# Glog_5G_LTE.net
KiCad netlist of a schematic drawn in Altium Designer
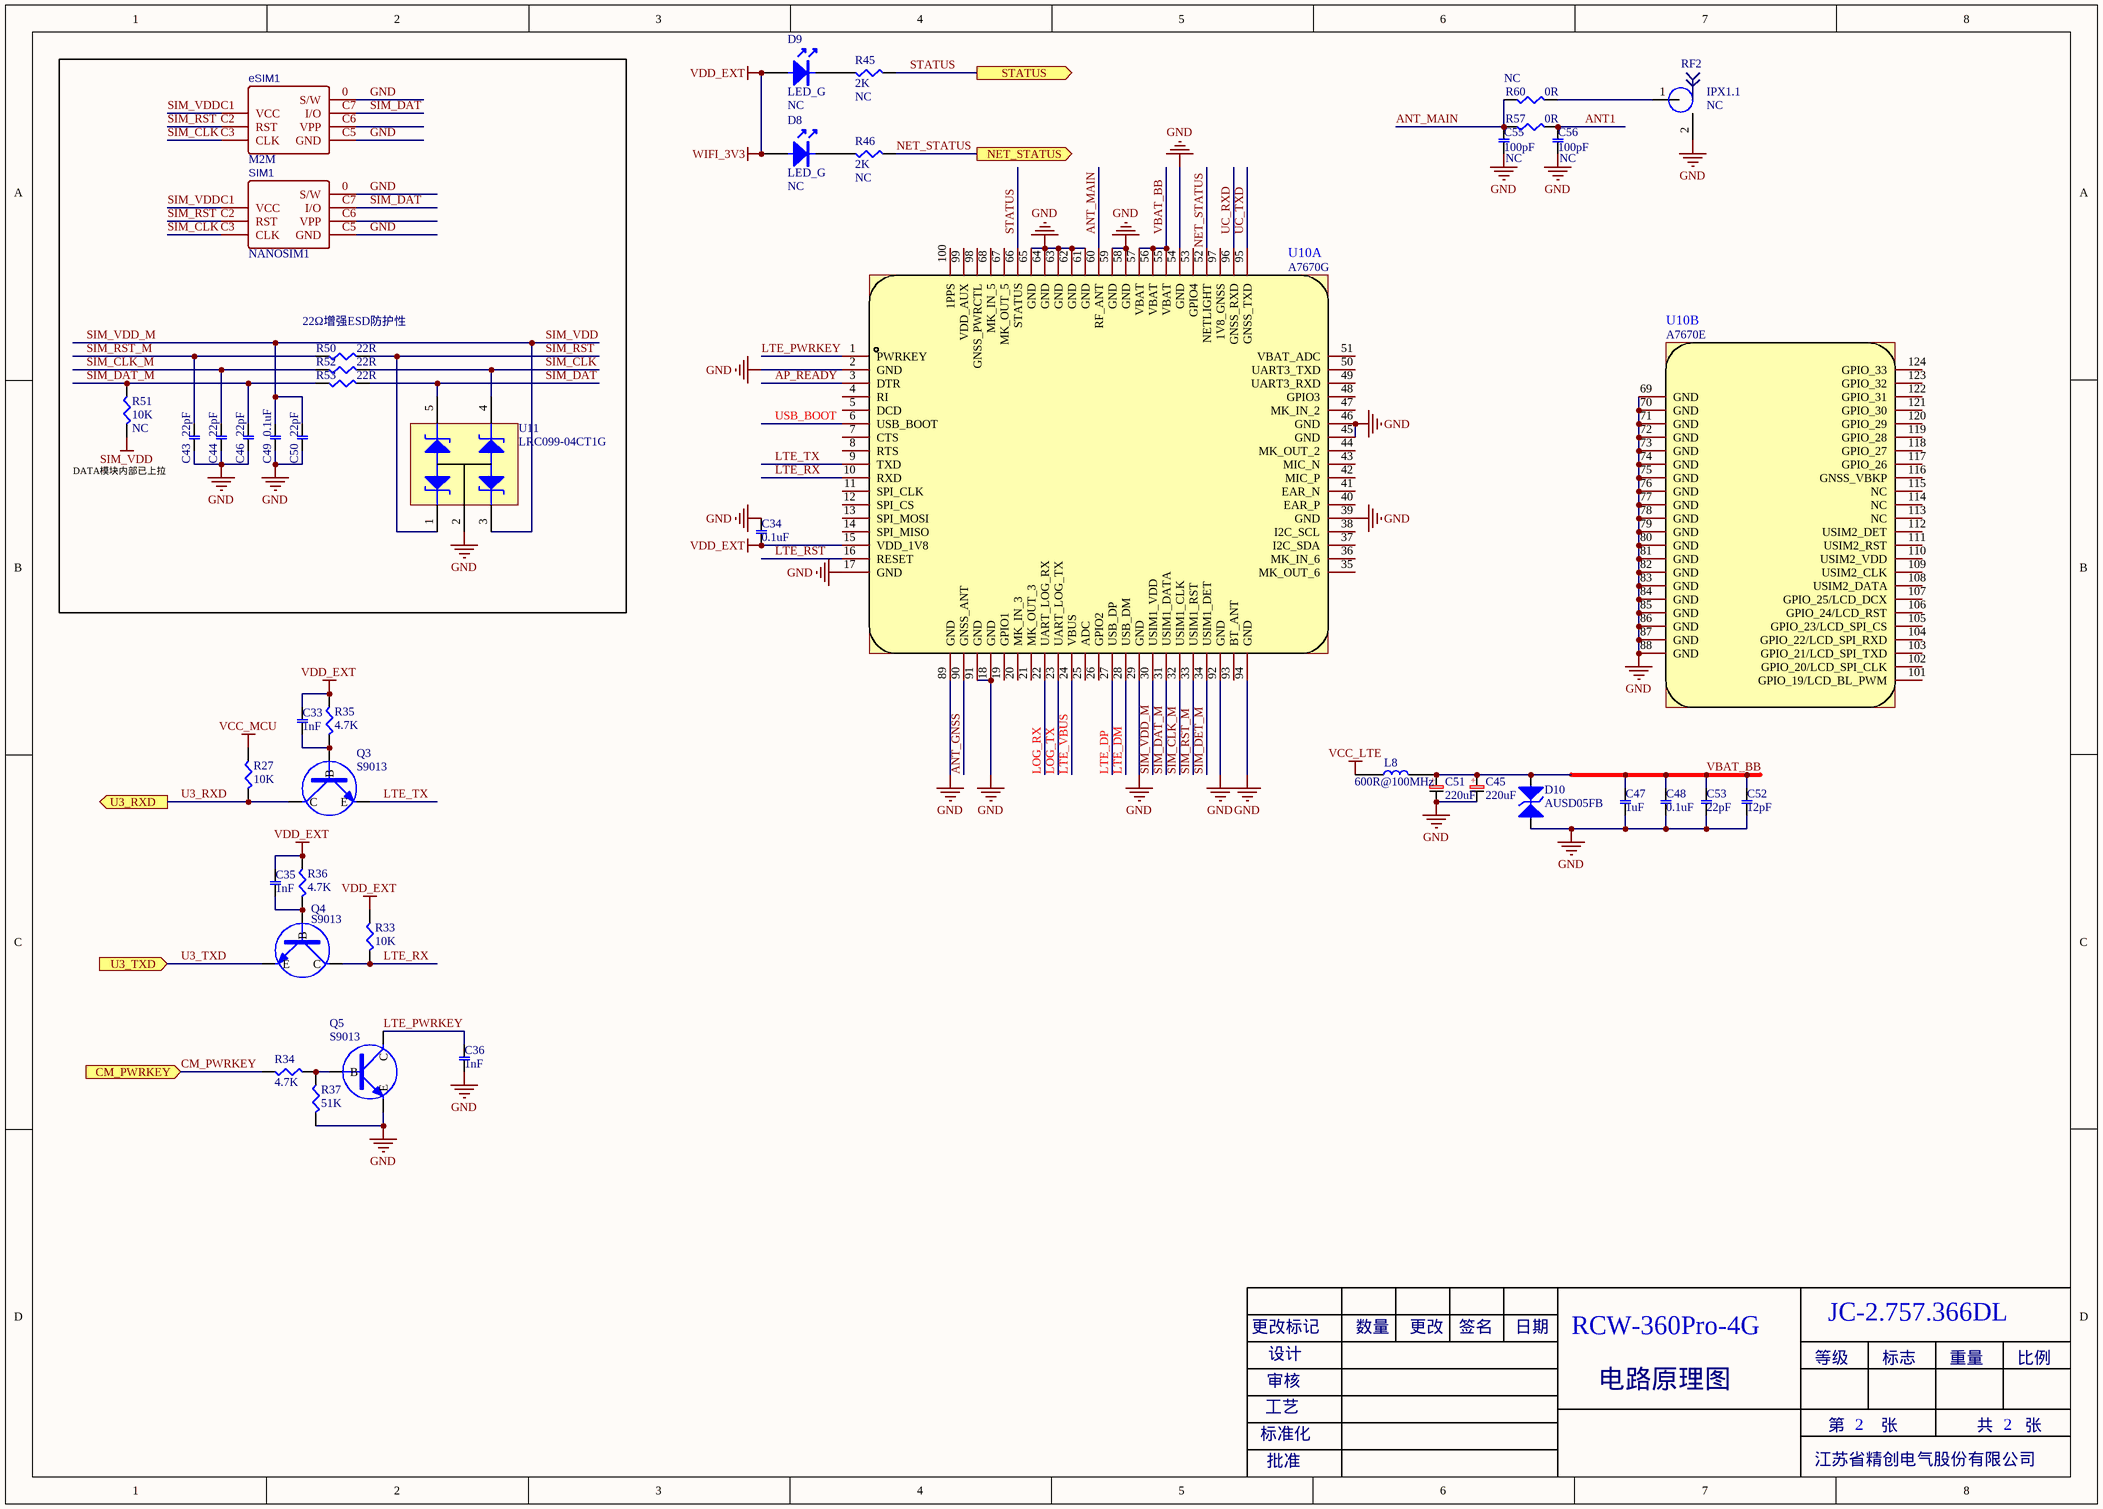
[diagram p0: Glog 5G_LTE.SchDoc]

(export (version "E")
  (design (tool "Eeschema 10.0.6"))
  (components
    (comp (ref "C33")
      (value "1nF")
      (footprint "0402C")
      (fields (field (name "VALUES") "1nF"))
      (libsource (lib "JC_ERP_DB") (part "Capacity-CE"))
    )
    (comp (ref "C34")
      (value "0.1uF")
      (footprint "0402C")
      (fields (field (name "VALUES") "0.1uF"))
      (libsource (lib "JC_ERP_DB") (part "Capacity-CE"))
    )
    (comp (ref "C35")
      (value "1nF")
      (footprint "0402C")
      (fields (field (name "VALUES") "1nF"))
      (libsource (lib "JC_ERP_DB") (part "Capacity-CE"))
    )
    (comp (ref "C36")
      (value "1nF")
      (footprint "0402C")
      (fields (field (name "VALUES") "1nF"))
      (libsource (lib "JC_ERP_DB") (part "Capacity-CE"))
    )
    (comp (ref "C43")
      (value "22pF")
      (footprint "0402C")
      (fields (field (name "VALUES") "22pF"))
      (libsource (lib "JC_ERP_DB") (part "Capacity-CE"))
    )
    (comp (ref "C44")
      (value "22pF")
      (footprint "0402C")
      (fields (field (name "VALUES") "22pF"))
      (libsource (lib "JC_ERP_DB") (part "Capacity-CE"))
    )
    (comp (ref "C45")
      (value "220uF")
      (footprint "3528C")
      (fields (field (name "VALUES") "220uF"))
      (libsource (lib "JC_ERP_DB") (part "Capacity-TA"))
    )
    (comp (ref "C46")
      (value "22pF")
      (footprint "0402C")
      (fields (field (name "VALUES") "22pF"))
      (libsource (lib "JC_ERP_DB") (part "Capacity-CE"))
    )
    (comp (ref "C47")
      (value "1uF")
      (footprint "0402C")
      (fields (field (name "VALUES") "1uF"))
      (libsource (lib "JC_ERP_DB") (part "Capacity-CE"))
    )
    (comp (ref "C48")
      (value "0.1uF")
      (footprint "0402C")
      (fields (field (name "VALUES") "0.1uF"))
      (libsource (lib "JC_ERP_DB") (part "Capacity-CE"))
    )
    (comp (ref "C49")
      (value "0.1uF")
      (footprint "0402C")
      (fields (field (name "VALUES") "0.1uF"))
      (libsource (lib "JC_ERP_DB") (part "Capacity-CE"))
    )
    (comp (ref "C50")
      (value "22pF")
      (footprint "0402C")
      (fields (field (name "VALUES") "22pF"))
      (libsource (lib "JC_ERP_DB") (part "Capacity-CE"))
    )
    (comp (ref "C51")
      (value "220uF")
      (footprint "3528C")
      (fields (field (name "VALUES") "220uF"))
      (libsource (lib "JC_ERP_DB") (part "Capacity-TA"))
    )
    (comp (ref "C52")
      (value "12pF")
      (footprint "0402C")
      (fields (field (name "VALUES") "12pF"))
      (libsource (lib "JC_ERP_DB") (part "Capacity-CE"))
    )
    (comp (ref "C53")
      (value "22pF")
      (footprint "0402C")
      (fields (field (name "VALUES") "22pF"))
      (libsource (lib "JC_ERP_DB") (part "Capacity-CE"))
    )
    (comp (ref "C55")
      (value "100pF")
      (footprint "0402C")
      (fields (field (name "VALUES") "100pF") (field (name "选焊") "NC"))
      (libsource (lib "JC_ERP_DB") (part "Capacity-CE"))
    )
    (comp (ref "C56")
      (value "100pF")
      (footprint "0402C")
      (fields (field (name "VALUES") "100pF") (field (name "选焊") "NC"))
      (libsource (lib "JC_ERP_DB") (part "Capacity-CE"))
    )
    (comp (ref "D8")
      (value "LED_G")
      (footprint "LED-0603")
      (fields (field (name "VALUES") "LED_G") (field (name "选焊") "NC"))
      (libsource (lib "JC_ERP_DB") (part "Diode-L"))
    )
    (comp (ref "D9")
      (value "LED_G")
      (footprint "LED-0603")
      (fields (field (name "VALUES") "LED_G") (field (name "选焊") "NC"))
      (libsource (lib "JC_ERP_DB") (part "Diode-L"))
    )
    (comp (ref "D10")
      (value "AUSD05FB")
      (footprint "BV05C")
      (fields (field (name "VALUES") "AUSD05FB"))
      (libsource (lib "JC_ERP_DB") (part "Diode-TVS"))
    )
    (comp (ref "eSIM1")
      (value "M2M")
      (footprint "QFN5*6-8")
      (fields (field (name "VALUES") "M2M"))
      (libsource (lib "JC_ERP_DB") (part "nano1.4_c77877"))
    )
    (comp (ref "L8")
      (value "600R@100MHz")
      (footprint "0603L")
      (fields (field (name "VALUES") "600R@100MHz"))
      (libsource (lib "JC_ERP_DB") (part "Inductor-SMT-2PIN"))
    )
    (comp (ref "Q3")
      (value "S9013")
      (footprint "SOT23-N")
      (fields (field (name "VALUES") "S9013"))
      (libsource (lib "JC_ERP_DB") (part "Dynatron-NPN"))
    )
    (comp (ref "Q4")
      (value "S9013")
      (footprint "SOT23-N")
      (fields (field (name "VALUES") "S9013"))
      (libsource (lib "JC_ERP_DB") (part "Dynatron-NPN"))
    )
    (comp (ref "Q5")
      (value "S9013")
      (footprint "SOT23-N")
      (fields (field (name "VALUES") "S9013"))
      (libsource (lib "JC_ERP_DB") (part "Dynatron-NPN"))
    )
    (comp (ref "R27")
      (value "10K")
      (footprint "0402R")
      (fields (field (name "VALUES") "10K"))
      (libsource (lib "JC_ERP_DB") (part "Resistors-SMT"))
    )
    (comp (ref "R33")
      (value "10K")
      (footprint "0402R")
      (fields (field (name "VALUES") "10K"))
      (libsource (lib "JC_ERP_DB") (part "Resistors-SMT"))
    )
    (comp (ref "R34")
      (value "4.7K")
      (footprint "0402R")
      (fields (field (name "VALUES") "4.7K"))
      (libsource (lib "JC_ERP_DB") (part "Resistors-SMT"))
    )
    (comp (ref "R35")
      (value "4.7K")
      (footprint "0402R")
      (fields (field (name "VALUES") "4.7K"))
      (libsource (lib "JC_ERP_DB") (part "Resistors-SMT"))
    )
    (comp (ref "R36")
      (value "4.7K")
      (footprint "0402R")
      (fields (field (name "VALUES") "4.7K"))
      (libsource (lib "JC_ERP_DB") (part "Resistors-SMT"))
    )
    (comp (ref "R37")
      (value "51K")
      (footprint "0402R")
      (fields (field (name "VALUES") "51K"))
      (libsource (lib "JC_ERP_DB") (part "Resistors-SMT"))
    )
    (comp (ref "R45")
      (value "2K")
      (footprint "0402R")
      (fields (field (name "VALUES") "2K") (field (name "选焊") "NC"))
      (libsource (lib "JC_ERP_DB") (part "Resistors-SMT"))
    )
    (comp (ref "R46")
      (value "2K")
      (footprint "0402R")
      (fields (field (name "VALUES") "2K") (field (name "选焊") "NC"))
      (libsource (lib "JC_ERP_DB") (part "Resistors-SMT"))
    )
    (comp (ref "R50")
      (value "22R")
      (footprint "0402R")
      (fields (field (name "VALUES") "22R"))
      (libsource (lib "JC_ERP_DB") (part "Resistors-SMT"))
    )
    (comp (ref "R51")
      (value "10K")
      (footprint "0402R")
      (fields (field (name "VALUES") "10K") (field (name "选焊") "NC"))
      (libsource (lib "JC_ERP_DB") (part "Resistors-SMT"))
    )
    (comp (ref "R52")
      (value "22R")
      (footprint "0402R")
      (fields (field (name "VALUES") "22R"))
      (libsource (lib "JC_ERP_DB") (part "Resistors-SMT"))
    )
    (comp (ref "R53")
      (value "22R")
      (footprint "0402R")
      (fields (field (name "VALUES") "22R"))
      (libsource (lib "JC_ERP_DB") (part "Resistors-SMT"))
    )
    (comp (ref "R57")
      (value "0R")
      (footprint "0402R")
      (fields (field (name "VALUES") "0R"))
      (libsource (lib "JC_ERP_DB") (part "Resistors-SMT"))
    )
    (comp (ref "R60")
      (value "0R")
      (footprint "0402R")
      (fields (field (name "VALUES") "0R") (field (name "选焊") "NC"))
      (libsource (lib "JC_ERP_DB") (part "Resistors-SMT"))
    )
    (comp (ref "RF2")
      (value "IPX1.1")
      (footprint "IPEX_3PIN")
      (fields (field (name "VALUES") "IPX1.1") (field (name "选焊") "NC"))
      (libsource (lib "JC_ERP_DB") (part "SMB-φ1.1mm"))
    )
    (comp (ref "SIM1")
      (value "NANOSIM1")
      (footprint "NANO_SIM SMT 翻盖式")
      (fields (field (name "VALUES") "NANOSIM1"))
      (libsource (lib "JC_ERP_DB") (part "nano1.4_c77877"))
    )
    (comp (ref "U10")
      (value "A7670E")
      (footprint "A7670xx")
      (fields (field (name "VALUES") "A7670E"))
      (libsource (lib "JC_ERP_DB") (part "A7670xx-LASE"))
    )
    (comp (ref "U11")
      (value "LRC099-04CT1G")
      (footprint "SOT-353")
      (fields (field (name "VALUES") "LRC099-04CT1G"))
      (libsource (lib "JC_ERP_DB") (part "Diode-TVS4"))
    )
  )
  (nets
    (net (code "1") (name "/ANT1") (class "Default")
      (node (ref "C56") (pin "1") (pintype "passive"))
      (node (ref "R57") (pin "2") (pinfunction "2_2") (pintype "passive"))
    )
    (net (code "2") (name "/ANT_GNSS") (class "Default")
      (node (ref "U10") (pin "90") (pinfunction "GNSS_ANT_90") (pintype "passive"))
    )
    (net (code "3") (name "/ANT_MAIN") (class "Default")
      (node (ref "C55") (pin "1") (pintype "passive"))
      (node (ref "R57") (pin "1") (pinfunction "1_1") (pintype "passive"))
      (node (ref "R60") (pin "1") (pinfunction "1_1") (pintype "passive"))
      (node (ref "U10") (pin "60") (pinfunction "RF_ANT_60") (pintype "passive"))
    )
    (net (code "4") (name "/AP_READY") (class "Default")
      (node (ref "U10") (pin "3") (pinfunction "DTR_3") (pintype "passive"))
    )
    (net (code "5") (name "/CM_PWRKEY") (class "Default")
      (node (ref "R34") (pin "2") (pinfunction "2_2") (pintype "passive"))
    )
    (net (code "6") (name "/LOG_RX") (class "Default")
      (node (ref "U10") (pin "22") (pinfunction "UART_LOG_RX_22") (pintype "passive"))
    )
    (net (code "7") (name "/LOG_TX") (class "Default")
      (node (ref "U10") (pin "23") (pinfunction "UART_LOG_TX_23") (pintype "passive"))
    )
    (net (code "8") (name "/LTE_DM") (class "Default")
      (node (ref "U10") (pin "28") (pinfunction "USB_DM_28") (pintype "passive"))
    )
    (net (code "9") (name "/LTE_DP") (class "Default")
      (node (ref "U10") (pin "27") (pinfunction "USB_DP_27") (pintype "passive"))
    )
    (net (code "10") (name "/LTE_PWRKEY") (class "Default")
      (node (ref "C36") (pin "2") (pintype "passive"))
      (node (ref "Q5") (pin "C") (pinfunction "C_C") (pintype "passive"))
      (node (ref "U10") (pin "1") (pinfunction "PWRKEY_1") (pintype "passive"))
    )
    (net (code "11") (name "/LTE_RST") (class "Default")
      (node (ref "U10") (pin "16") (pinfunction "RESET_16") (pintype "passive"))
    )
    (net (code "12") (name "/LTE_RX") (class "Default")
      (node (ref "Q4") (pin "C") (pinfunction "C_C") (pintype "passive"))
      (node (ref "R33") (pin "2") (pinfunction "2_2") (pintype "passive"))
      (node (ref "U10") (pin "10") (pinfunction "RXD_10") (pintype "passive"))
    )
    (net (code "13") (name "/LTE_TX") (class "Default")
      (node (ref "Q3") (pin "E") (pinfunction "E_E") (pintype "passive"))
      (node (ref "U10") (pin "9") (pinfunction "TXD_9") (pintype "passive"))
    )
    (net (code "14") (name "/LTE_VBUS") (class "Default")
      (node (ref "U10") (pin "24") (pinfunction "VBUS_24") (pintype "passive"))
    )
    (net (code "15") (name "/NET_STATUS") (class "Default")
      (node (ref "R46") (pin "1") (pinfunction "1_1") (pintype "passive"))
      (node (ref "U10") (pin "52") (pinfunction "NETLIGHT_52") (pintype "passive"))
    )
    (net (code "16") (name "/SIM_CLK") (class "Default")
      (node (ref "R52") (pin "2") (pinfunction "2_2") (pintype "passive"))
      (node (ref "SIM1") (pin "C3") (pinfunction "CLK_C3") (pintype "passive"))
      (node (ref "U11") (pin "4") (pintype "passive"))
      (node (ref "eSIM1") (pin "C3") (pinfunction "CLK_C3") (pintype "passive"))
    )
    (net (code "17") (name "/SIM_CLK_M") (class "Default")
      (node (ref "C44") (pin "2") (pintype "passive"))
      (node (ref "R52") (pin "1") (pinfunction "1_1") (pintype "passive"))
      (node (ref "U10") (pin "32") (pinfunction "USIM1_CLK_32") (pintype "passive"))
    )
    (net (code "18") (name "/SIM_DAT") (class "Default")
      (node (ref "R53") (pin "2") (pinfunction "2_2") (pintype "passive"))
      (node (ref "SIM1") (pin "C7") (pinfunction "I/O_C7") (pintype "passive"))
      (node (ref "U11") (pin "5") (pintype "passive"))
      (node (ref "eSIM1") (pin "C7") (pinfunction "I/O_C7") (pintype "passive"))
    )
    (net (code "19") (name "/SIM_DAT_M") (class "Default")
      (node (ref "C46") (pin "2") (pintype "passive"))
      (node (ref "R51") (pin "2") (pinfunction "2_2") (pintype "passive"))
      (node (ref "R53") (pin "1") (pinfunction "1_1") (pintype "passive"))
      (node (ref "U10") (pin "31") (pinfunction "USIM1_DATA_31") (pintype "passive"))
    )
    (net (code "20") (name "/SIM_DET_M") (class "Default")
      (node (ref "U10") (pin "34") (pinfunction "USIM1_DET_34") (pintype "passive"))
    )
    (net (code "21") (name "/SIM_RST") (class "Default")
      (node (ref "R50") (pin "2") (pinfunction "2_2") (pintype "passive"))
      (node (ref "SIM1") (pin "C2") (pinfunction "RST_C2") (pintype "passive"))
      (node (ref "U11") (pin "1") (pintype "passive"))
      (node (ref "eSIM1") (pin "C2") (pinfunction "RST_C2") (pintype "passive"))
    )
    (net (code "22") (name "/SIM_RST_M") (class "Default")
      (node (ref "C43") (pin "2") (pintype "passive"))
      (node (ref "R50") (pin "1") (pinfunction "1_1") (pintype "passive"))
      (node (ref "U10") (pin "33") (pinfunction "USIM1_RST_33") (pintype "passive"))
    )
    (net (code "23") (name "/STATUS") (class "Default")
      (node (ref "R45") (pin "1") (pinfunction "1_1") (pintype "passive"))
      (node (ref "U10") (pin "66") (pinfunction "STATUS_66") (pintype "passive"))
    )
    (net (code "24") (name "/U3_RXD") (class "Default")
      (node (ref "Q3") (pin "C") (pinfunction "C_C") (pintype "passive"))
      (node (ref "R27") (pin "2") (pinfunction "2_2") (pintype "passive"))
    )
    (net (code "25") (name "/U3_TXD") (class "Default")
      (node (ref "Q4") (pin "E") (pinfunction "E_E") (pintype "passive"))
    )
    (net (code "26") (name "/UC_RXD") (class "Default")
      (node (ref "U10") (pin "96") (pinfunction "GNSS_RXD_96") (pintype "passive"))
    )
    (net (code "27") (name "/UC_TXD") (class "Default")
      (node (ref "U10") (pin "95") (pinfunction "GNSS_TXD_95") (pintype "passive"))
    )
    (net (code "28") (name "/USB_BOOT") (class "Default")
      (node (ref "U10") (pin "6") (pinfunction "USB_BOOT_6") (pintype "passive"))
    )
    (net (code "29") (name "/VBAT_BB") (class "Default")
      (node (ref "C45") (pin "1") (pintype "passive"))
      (node (ref "C47") (pin "1") (pintype "passive"))
      (node (ref "C48") (pin "1") (pintype "passive"))
      (node (ref "C51") (pin "1") (pintype "passive"))
      (node (ref "C52") (pin "2") (pintype "passive"))
      (node (ref "C53") (pin "2") (pintype "passive"))
      (node (ref "D10") (pin "1") (pinfunction "A_1") (pintype "passive"))
      (node (ref "L8") (pin "2") (pinfunction "2_2") (pintype "passive"))
      (node (ref "U10") (pin "55") (pinfunction "VBAT_55") (pintype "passive"))
      (node (ref "U10") (pin "56") (pinfunction "VBAT_56") (pintype "passive"))
      (node (ref "U10") (pin "57") (pinfunction "VBAT_57") (pintype "passive"))
    )
    (net (code "30") (name "GND") (class "Default")
      (node (ref "C34") (pin "2") (pintype "passive"))
      (node (ref "C36") (pin "1") (pintype "passive"))
      (node (ref "C43") (pin "1") (pintype "passive"))
      (node (ref "C44") (pin "1") (pintype "passive"))
      (node (ref "C45") (pin "2") (pintype "passive"))
      (node (ref "C46") (pin "1") (pintype "passive"))
      (node (ref "C47") (pin "2") (pintype "passive"))
      (node (ref "C48") (pin "2") (pintype "passive"))
      (node (ref "C49") (pin "2") (pintype "passive"))
      (node (ref "C50") (pin "1") (pintype "passive"))
      (node (ref "C51") (pin "2") (pintype "passive"))
      (node (ref "C52") (pin "1") (pintype "passive"))
      (node (ref "C53") (pin "1") (pintype "passive"))
      (node (ref "C55") (pin "2") (pintype "passive"))
      (node (ref "C56") (pin "2") (pintype "passive"))
      (node (ref "D10") (pin "2") (pinfunction "K_2") (pintype "passive"))
      (node (ref "Q5") (pin "E") (pinfunction "E_E") (pintype "passive"))
      (node (ref "R37") (pin "2") (pinfunction "2_2") (pintype "passive"))
      (node (ref "RF2") (pin "2") (pinfunction "2_2") (pintype "passive"))
      (node (ref "SIM1") (pin "0") (pinfunction "S/W_0") (pintype "passive"))
      (node (ref "SIM1") (pin "C5") (pinfunction "GND_C5") (pintype "passive"))
      (node (ref "U10") (pin "17") (pinfunction "GND_17") (pintype "passive"))
      (node (ref "U10") (pin "18") (pinfunction "GND_18") (pintype "passive"))
      (node (ref "U10") (pin "2") (pinfunction "GND_2") (pintype "passive"))
      (node (ref "U10") (pin "29") (pinfunction "GND_29") (pintype "passive"))
      (node (ref "U10") (pin "39") (pinfunction "GND_39") (pintype "passive"))
      (node (ref "U10") (pin "45") (pinfunction "GND_45") (pintype "passive"))
      (node (ref "U10") (pin "46") (pinfunction "GND_46") (pintype "passive"))
      (node (ref "U10") (pin "54") (pinfunction "GND_54") (pintype "passive"))
      (node (ref "U10") (pin "58") (pinfunction "GND_58") (pintype "passive"))
      (node (ref "U10") (pin "59") (pinfunction "GND_59") (pintype "passive"))
      (node (ref "U10") (pin "61") (pinfunction "GND_61") (pintype "passive"))
      (node (ref "U10") (pin "62") (pinfunction "GND_62") (pintype "passive"))
      (node (ref "U10") (pin "63") (pinfunction "GND_63") (pintype "passive"))
      (node (ref "U10") (pin "64") (pinfunction "GND_64") (pintype "passive"))
      (node (ref "U10") (pin "65") (pinfunction "GND_65") (pintype "passive"))
      (node (ref "U10") (pin "69") (pinfunction "GND_69") (pintype "passive"))
      (node (ref "U10") (pin "70") (pinfunction "GND_70") (pintype "passive"))
      (node (ref "U10") (pin "71") (pinfunction "GND_71") (pintype "passive"))
      (node (ref "U10") (pin "72") (pinfunction "GND_72") (pintype "passive"))
      (node (ref "U10") (pin "73") (pinfunction "GND_73") (pintype "passive"))
      (node (ref "U10") (pin "74") (pinfunction "GND_74") (pintype "passive"))
      (node (ref "U10") (pin "75") (pinfunction "GND_75") (pintype "passive"))
      (node (ref "U10") (pin "76") (pinfunction "GND_76") (pintype "passive"))
      (node (ref "U10") (pin "77") (pinfunction "GND_77") (pintype "passive"))
      (node (ref "U10") (pin "78") (pinfunction "GND_78") (pintype "passive"))
      (node (ref "U10") (pin "79") (pinfunction "GND_79") (pintype "passive"))
      (node (ref "U10") (pin "80") (pinfunction "GND_80") (pintype "passive"))
      (node (ref "U10") (pin "81") (pinfunction "GND_81") (pintype "passive"))
      (node (ref "U10") (pin "82") (pinfunction "GND_82") (pintype "passive"))
      (node (ref "U10") (pin "83") (pinfunction "GND_83") (pintype "passive"))
      (node (ref "U10") (pin "84") (pinfunction "GND_84") (pintype "passive"))
      (node (ref "U10") (pin "85") (pinfunction "GND_85") (pintype "passive"))
      (node (ref "U10") (pin "86") (pinfunction "GND_86") (pintype "passive"))
      (node (ref "U10") (pin "87") (pinfunction "GND_87") (pintype "passive"))
      (node (ref "U10") (pin "88") (pinfunction "GND_88") (pintype "passive"))
      (node (ref "U10") (pin "89") (pinfunction "GND_89") (pintype "passive"))
      (node (ref "U10") (pin "91") (pinfunction "GND_91") (pintype "passive"))
      (node (ref "U10") (pin "92") (pinfunction "GND_92") (pintype "passive"))
      (node (ref "U10") (pin "94") (pinfunction "GND_94") (pintype "passive"))
      (node (ref "U11") (pin "2") (pintype "passive"))
      (node (ref "eSIM1") (pin "0") (pinfunction "S/W_0") (pintype "passive"))
      (node (ref "eSIM1") (pin "C5") (pinfunction "GND_C5") (pintype "passive"))
    )
    (net (code "31") (name "Net-(C33-Pad1)") (class "Default")
      (node (ref "C33") (pin "1") (pintype "passive"))
      (node (ref "Q3") (pin "B") (pinfunction "B_B") (pintype "passive"))
      (node (ref "R35") (pin "1") (pinfunction "1_1") (pintype "passive"))
    )
    (net (code "32") (name "Net-(C35-Pad1)") (class "Default")
      (node (ref "C35") (pin "1") (pintype "passive"))
      (node (ref "Q4") (pin "B") (pinfunction "B_B") (pintype "passive"))
      (node (ref "R36") (pin "1") (pinfunction "1_1") (pintype "passive"))
    )
    (net (code "33") (name "Net-(D8-K)") (class "Default")
      (node (ref "D8") (pin "2") (pinfunction "K_2") (pintype "passive"))
      (node (ref "R46") (pin "2") (pinfunction "2_2") (pintype "passive"))
    )
    (net (code "34") (name "Net-(D9-K)") (class "Default")
      (node (ref "D9") (pin "2") (pinfunction "K_2") (pintype "passive"))
      (node (ref "R45") (pin "2") (pinfunction "2_2") (pintype "passive"))
    )
    (net (code "35") (name "Net-(Q5-PadB)") (class "Default")
      (node (ref "Q5") (pin "B") (pinfunction "B_B") (pintype "passive"))
      (node (ref "R34") (pin "1") (pinfunction "1_1") (pintype "passive"))
      (node (ref "R37") (pin "1") (pinfunction "1_1") (pintype "passive"))
    )
    (net (code "36") (name "Net-(R60-Pad2)") (class "Default")
      (node (ref "R60") (pin "2") (pinfunction "2_2") (pintype "passive"))
      (node (ref "RF2") (pin "1") (pinfunction "1_1") (pintype "passive"))
    )
    (net (code "37") (name "SIM_VDD") (class "Default")
      (node (ref "C49") (pin "1") (pintype "passive"))
      (node (ref "C50") (pin "2") (pintype "passive"))
      (node (ref "R51") (pin "1") (pinfunction "1_1") (pintype "passive"))
      (node (ref "SIM1") (pin "C1") (pinfunction "VCC_C1") (pintype "passive"))
      (node (ref "U10") (pin "30") (pinfunction "USIM1_VDD_30") (pintype "passive"))
      (node (ref "U11") (pin "3") (pintype "passive"))
      (node (ref "eSIM1") (pin "C1") (pinfunction "VCC_C1") (pintype "passive"))
    )
    (net (code "38") (name "VCC_LTE") (class "Default")
      (node (ref "L8") (pin "1") (pinfunction "1_1") (pintype "passive"))
    )
    (net (code "39") (name "VCC_MCU") (class "Default")
      (node (ref "R27") (pin "1") (pinfunction "1_1") (pintype "passive"))
    )
    (net (code "40") (name "VDD_EXT") (class "Default")
      (node (ref "C33") (pin "2") (pintype "passive"))
      (node (ref "C34") (pin "1") (pintype "passive"))
      (node (ref "C35") (pin "2") (pintype "passive"))
      (node (ref "D8") (pin "1") (pinfunction "A_1") (pintype "passive"))
      (node (ref "D9") (pin "1") (pinfunction "A_1") (pintype "passive"))
      (node (ref "R33") (pin "1") (pinfunction "1_1") (pintype "passive"))
      (node (ref "R35") (pin "2") (pinfunction "2_2") (pintype "passive"))
      (node (ref "R36") (pin "2") (pinfunction "2_2") (pintype "passive"))
      (node (ref "U10") (pin "15") (pinfunction "VDD_1V8_15") (pintype "passive"))
    )
    (net (code "41") (name "unconnected-(SIM1-VPP-PadC6)") (class "Default")
      (node (ref "SIM1") (pin "C6") (pinfunction "VPP_C6") (pintype "passive"))
    )
    (net (code "42") (name "unconnected-(U10A-1PPS-Pad100)") (class "Default")
      (node (ref "U10") (pin "100") (pinfunction "1PPS_100") (pintype "passive"))
    )
    (net (code "43") (name "unconnected-(U10A-1V8_GNSS-Pad97)") (class "Default")
      (node (ref "U10") (pin "97") (pinfunction "1V8_GNSS_97") (pintype "passive"))
    )
    (net (code "44") (name "unconnected-(U10A-ADC-Pad25)") (class "Default")
      (node (ref "U10") (pin "25") (pinfunction "ADC_25") (pintype "passive"))
    )
    (net (code "45") (name "unconnected-(U10A-BT_ANT-Pad93)") (class "Default")
      (node (ref "U10") (pin "93") (pinfunction "BT_ANT_93") (pintype "passive"))
    )
    (net (code "46") (name "unconnected-(U10A-CTS-Pad7)") (class "Default")
      (node (ref "U10") (pin "7") (pinfunction "CTS_7") (pintype "passive"))
    )
    (net (code "47") (name "unconnected-(U10A-DCD-Pad5)") (class "Default")
      (node (ref "U10") (pin "5") (pinfunction "DCD_5") (pintype "passive"))
    )
    (net (code "48") (name "unconnected-(U10A-EAR_N-Pad41)") (class "Default")
      (node (ref "U10") (pin "41") (pinfunction "EAR_N_41") (pintype "passive"))
    )
    (net (code "49") (name "unconnected-(U10A-EAR_P-Pad40)") (class "Default")
      (node (ref "U10") (pin "40") (pinfunction "EAR_P_40") (pintype "passive"))
    )
    (net (code "50") (name "unconnected-(U10A-GNSS_PWRCTL-Pad98)") (class "Default")
      (node (ref "U10") (pin "98") (pinfunction "GNSS_PWRCTL_98") (pintype "passive"))
    )
    (net (code "51") (name "unconnected-(U10A-GPIO1-Pad19)") (class "Default")
      (node (ref "U10") (pin "19") (pinfunction "GPIO1_19") (pintype "passive"))
    )
    (net (code "52") (name "unconnected-(U10A-GPIO2-Pad26)") (class "Default")
      (node (ref "U10") (pin "26") (pinfunction "GPIO2_26") (pintype "passive"))
    )
    (net (code "53") (name "unconnected-(U10A-GPIO3-Pad48)") (class "Default")
      (node (ref "U10") (pin "48") (pinfunction "GPIO3_48") (pintype "passive"))
    )
    (net (code "54") (name "unconnected-(U10A-GPIO4-Pad53)") (class "Default")
      (node (ref "U10") (pin "53") (pinfunction "GPIO4_53") (pintype "passive"))
    )
    (net (code "55") (name "unconnected-(U10A-I2C_SCL-Pad38)") (class "Default")
      (node (ref "U10") (pin "38") (pinfunction "I2C_SCL_38") (pintype "passive"))
    )
    (net (code "56") (name "unconnected-(U10A-I2C_SDA-Pad37)") (class "Default")
      (node (ref "U10") (pin "37") (pinfunction "I2C_SDA_37") (pintype "passive"))
    )
    (net (code "57") (name "unconnected-(U10A-MIC_N-Pad43)") (class "Default")
      (node (ref "U10") (pin "43") (pinfunction "MIC_N_43") (pintype "passive"))
    )
    (net (code "58") (name "unconnected-(U10A-MIC_P-Pad42)") (class "Default")
      (node (ref "U10") (pin "42") (pinfunction "MIC_P_42") (pintype "passive"))
    )
    (net (code "59") (name "unconnected-(U10A-MK_IN_2-Pad47)") (class "Default")
      (node (ref "U10") (pin "47") (pinfunction "MK_IN_2_47") (pintype "passive"))
    )
    (net (code "60") (name "unconnected-(U10A-MK_IN_3-Pad20)") (class "Default")
      (node (ref "U10") (pin "20") (pinfunction "MK_IN_3_20") (pintype "passive"))
    )
    (net (code "61") (name "unconnected-(U10A-MK_IN_5-Pad68)") (class "Default")
      (node (ref "U10") (pin "68") (pinfunction "MK_IN_5_68") (pintype "passive"))
    )
    (net (code "62") (name "unconnected-(U10A-MK_IN_6-Pad36)") (class "Default")
      (node (ref "U10") (pin "36") (pinfunction "MK_IN_6_36") (pintype "passive"))
    )
    (net (code "63") (name "unconnected-(U10A-MK_OUT_2-Pad44)") (class "Default")
      (node (ref "U10") (pin "44") (pinfunction "MK_OUT_2_44") (pintype "passive"))
    )
    (net (code "64") (name "unconnected-(U10A-MK_OUT_3-Pad21)") (class "Default")
      (node (ref "U10") (pin "21") (pinfunction "MK_OUT_3_21") (pintype "passive"))
    )
    (net (code "65") (name "unconnected-(U10A-MK_OUT_5-Pad67)") (class "Default")
      (node (ref "U10") (pin "67") (pinfunction "MK_OUT_5_67") (pintype "passive"))
    )
    (net (code "66") (name "unconnected-(U10A-MK_OUT_6-Pad35)") (class "Default")
      (node (ref "U10") (pin "35") (pinfunction "MK_OUT_6_35") (pintype "passive"))
    )
    (net (code "67") (name "unconnected-(U10A-RI-Pad4)") (class "Default")
      (node (ref "U10") (pin "4") (pinfunction "RI_4") (pintype "passive"))
    )
    (net (code "68") (name "unconnected-(U10A-RTS-Pad8)") (class "Default")
      (node (ref "U10") (pin "8") (pinfunction "RTS_8") (pintype "passive"))
    )
    (net (code "69") (name "unconnected-(U10A-SPI_CLK-Pad11)") (class "Default")
      (node (ref "U10") (pin "11") (pinfunction "SPI_CLK_11") (pintype "passive"))
    )
    (net (code "70") (name "unconnected-(U10A-SPI_CS-Pad12)") (class "Default")
      (node (ref "U10") (pin "12") (pinfunction "SPI_CS_12") (pintype "passive"))
    )
    (net (code "71") (name "unconnected-(U10A-SPI_MISO-Pad14)") (class "Default")
      (node (ref "U10") (pin "14") (pinfunction "SPI_MISO_14") (pintype "passive"))
    )
    (net (code "72") (name "unconnected-(U10A-SPI_MOSI-Pad13)") (class "Default")
      (node (ref "U10") (pin "13") (pinfunction "SPI_MOSI_13") (pintype "passive"))
    )
    (net (code "73") (name "unconnected-(U10A-UART3_RXD-Pad49)") (class "Default")
      (node (ref "U10") (pin "49") (pinfunction "UART3_RXD_49") (pintype "passive"))
    )
    (net (code "74") (name "unconnected-(U10A-UART3_TXD-Pad50)") (class "Default")
      (node (ref "U10") (pin "50") (pinfunction "UART3_TXD_50") (pintype "passive"))
    )
    (net (code "75") (name "unconnected-(U10A-VBAT_ADC-Pad51)") (class "Default")
      (node (ref "U10") (pin "51") (pinfunction "VBAT_ADC_51") (pintype "passive"))
    )
    (net (code "76") (name "unconnected-(U10A-VDD_AUX-Pad99)") (class "Default")
      (node (ref "U10") (pin "99") (pinfunction "VDD_AUX_99") (pintype "passive"))
    )
    (net (code "77") (name "unconnected-(U10B-GNSS_VBKP-Pad116)") (class "Default")
      (node (ref "U10") (pin "116") (pinfunction "GNSS_VBKP_116") (pintype "passive"))
    )
    (net (code "78") (name "unconnected-(U10B-GPIO_19{slash}LCD_BL_PWM-Pad101)") (class "Default")
      (node (ref "U10") (pin "101") (pinfunction "GPIO_19/LCD_BL_PWM_101") (pintype "passive"))
    )
    (net (code "79") (name "unconnected-(U10B-GPIO_20{slash}LCD_SPI_CLK-Pad102)") (class "Default")
      (node (ref "U10") (pin "102") (pinfunction "GPIO_20/LCD_SPI_CLK_102") (pintype "passive"))
    )
    (net (code "80") (name "unconnected-(U10B-GPIO_21{slash}LCD_SPI_TXD-Pad103)") (class "Default")
      (node (ref "U10") (pin "103") (pinfunction "GPIO_21/LCD_SPI_TXD_103") (pintype "passive"))
    )
    (net (code "81") (name "unconnected-(U10B-GPIO_22{slash}LCD_SPI_RXD-Pad104)") (class "Default")
      (node (ref "U10") (pin "104") (pinfunction "GPIO_22/LCD_SPI_RXD_104") (pintype "passive"))
    )
    (net (code "82") (name "unconnected-(U10B-GPIO_23{slash}LCD_SPI_CS-Pad105)") (class "Default")
      (node (ref "U10") (pin "105") (pinfunction "GPIO_23/LCD_SPI_CS_105") (pintype "passive"))
    )
    (net (code "83") (name "unconnected-(U10B-GPIO_24{slash}LCD_RST-Pad106)") (class "Default")
      (node (ref "U10") (pin "106") (pinfunction "GPIO_24/LCD_RST_106") (pintype "passive"))
    )
    (net (code "84") (name "unconnected-(U10B-GPIO_25{slash}LCD_DCX-Pad107)") (class "Default")
      (node (ref "U10") (pin "107") (pinfunction "GPIO_25/LCD_DCX_107") (pintype "passive"))
    )
    (net (code "85") (name "unconnected-(U10B-GPIO_26-Pad117)") (class "Default")
      (node (ref "U10") (pin "117") (pinfunction "GPIO_26_117") (pintype "passive"))
    )
    (net (code "86") (name "unconnected-(U10B-GPIO_27-Pad118)") (class "Default")
      (node (ref "U10") (pin "118") (pinfunction "GPIO_27_118") (pintype "passive"))
    )
    (net (code "87") (name "unconnected-(U10B-GPIO_28-Pad119)") (class "Default")
      (node (ref "U10") (pin "119") (pinfunction "GPIO_28_119") (pintype "passive"))
    )
    (net (code "88") (name "unconnected-(U10B-GPIO_29-Pad120)") (class "Default")
      (node (ref "U10") (pin "120") (pinfunction "GPIO_29_120") (pintype "passive"))
    )
    (net (code "89") (name "unconnected-(U10B-GPIO_30-Pad121)") (class "Default")
      (node (ref "U10") (pin "121") (pinfunction "GPIO_30_121") (pintype "passive"))
    )
    (net (code "90") (name "unconnected-(U10B-GPIO_31-Pad122)") (class "Default")
      (node (ref "U10") (pin "122") (pinfunction "GPIO_31_122") (pintype "passive"))
    )
    (net (code "91") (name "unconnected-(U10B-GPIO_32-Pad123)") (class "Default")
      (node (ref "U10") (pin "123") (pinfunction "GPIO_32_123") (pintype "passive"))
    )
    (net (code "92") (name "unconnected-(U10B-GPIO_33-Pad124)") (class "Default")
      (node (ref "U10") (pin "124") (pinfunction "GPIO_33_124") (pintype "passive"))
    )
    (net (code "93") (name "unconnected-(U10B-NC-Pad113)") (class "Default")
      (node (ref "U10") (pin "113") (pinfunction "NC_113") (pintype "passive"))
    )
    (net (code "94") (name "unconnected-(U10B-NC-Pad114)") (class "Default")
      (node (ref "U10") (pin "114") (pinfunction "NC_114") (pintype "passive"))
    )
    (net (code "95") (name "unconnected-(U10B-NC-Pad115)") (class "Default")
      (node (ref "U10") (pin "115") (pinfunction "NC_115") (pintype "passive"))
    )
    (net (code "96") (name "unconnected-(U10B-USIM2_CLK-Pad109)") (class "Default")
      (node (ref "U10") (pin "109") (pinfunction "USIM2_CLK_109") (pintype "passive"))
    )
    (net (code "97") (name "unconnected-(U10B-USIM2_DATA-Pad108)") (class "Default")
      (node (ref "U10") (pin "108") (pinfunction "USIM2_DATA_108") (pintype "passive"))
    )
    (net (code "98") (name "unconnected-(U10B-USIM2_DET-Pad112)") (class "Default")
      (node (ref "U10") (pin "112") (pinfunction "USIM2_DET_112") (pintype "passive"))
    )
    (net (code "99") (name "unconnected-(U10B-USIM2_RST-Pad111)") (class "Default")
      (node (ref "U10") (pin "111") (pinfunction "USIM2_RST_111") (pintype "passive"))
    )
    (net (code "100") (name "unconnected-(U10B-USIM2_VDD-Pad110)") (class "Default")
      (node (ref "U10") (pin "110") (pinfunction "USIM2_VDD_110") (pintype "passive"))
    )
    (net (code "101") (name "unconnected-(eSIM1-VPP-PadC6)") (class "Default")
      (node (ref "eSIM1") (pin "C6") (pinfunction "VPP_C6") (pintype "passive"))
    )
  )
)
